# rgb-svid.net
KiCad netlist of a schematic drawn in EAGLE
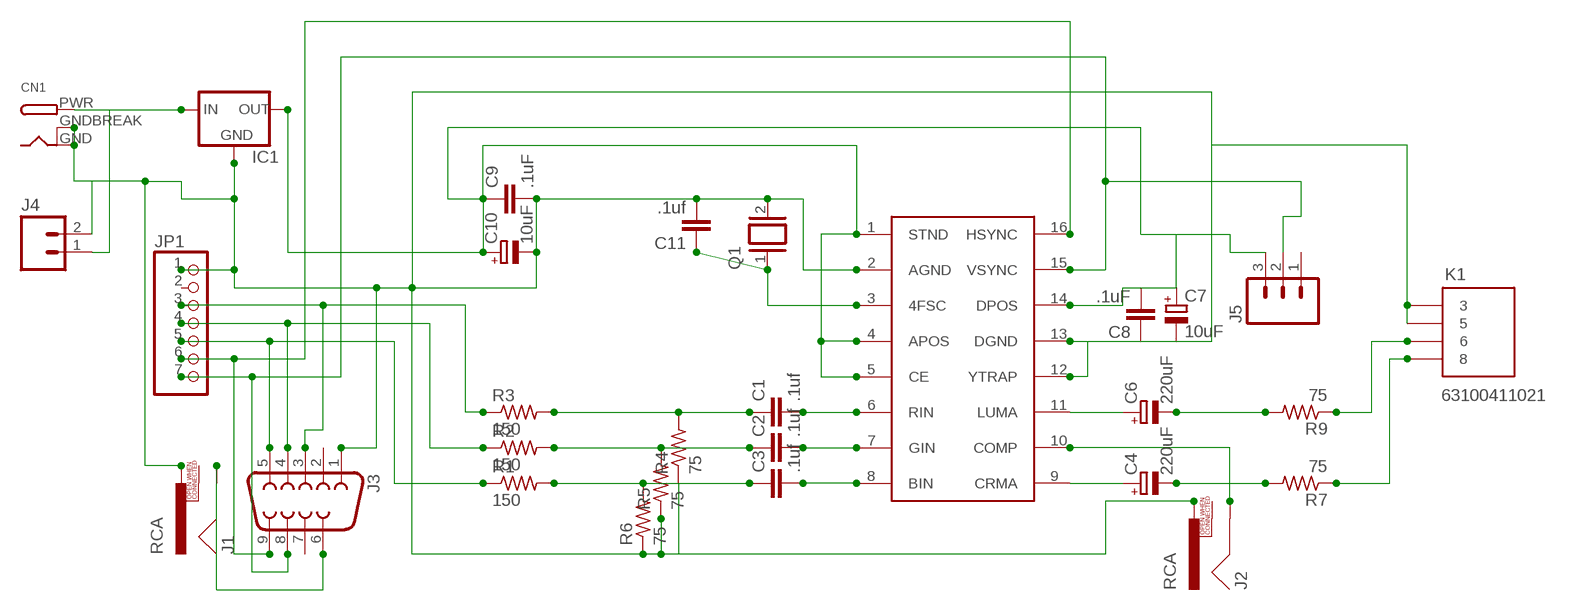
[diagram p0: schematic, sheet 1]

(export (version "E")
  (design (tool "Eeschema 10.0.6"))
  (components
    (comp (ref "C1")
      (value ".1uf")
      (footprint "eagle-import:C2.5-2")
      (libsource (lib "eagle-import") (part "C2.5/2"))
    )
    (comp (ref "C2")
      (value ".1uf")
      (footprint "eagle-import:C2.5-2")
      (libsource (lib "eagle-import") (part "C2.5/2"))
    )
    (comp (ref "C3")
      (value ".1uf")
      (footprint "eagle-import:C2.5-2")
      (libsource (lib "eagle-import") (part "C2.5/2"))
    )
    (comp (ref "C4")
      (value "220uF")
      (footprint "eagle-import:E2-5")
      (libsource (lib "eagle-import") (part "CPOL-EUE2-5"))
    )
    (comp (ref "C6")
      (value "220uF")
      (footprint "eagle-import:E2-5")
      (libsource (lib "eagle-import") (part "CPOL-EUE2-5"))
    )
    (comp (ref "C7")
      (value "10uF")
      (footprint "eagle-import:E2-5")
      (libsource (lib "eagle-import") (part "CPOL-EUE2-5"))
    )
    (comp (ref "C8")
      (value ".1uF")
      (footprint "eagle-import:C2.5-2")
      (libsource (lib "eagle-import") (part "C2.5/2"))
    )
    (comp (ref "C9")
      (value ".1uF")
      (footprint "eagle-import:C2.5-2")
      (libsource (lib "eagle-import") (part "C2.5/2"))
    )
    (comp (ref "C10")
      (value "10uF")
      (footprint "eagle-import:E2-5")
      (libsource (lib "eagle-import") (part "CPOL-EUE2-5"))
    )
    (comp (ref "C11")
      (value ".1uf")
      (footprint "eagle-import:C2.5-2")
      (libsource (lib "eagle-import") (part "C2.5/2"))
    )
    (comp (ref "CN1")
      (value "DCBARRELPTH")
      (footprint "eagle-import:DCJACK_2MM_PTH")
      (libsource (lib "eagle-import") (part "DCBARRELPTH"))
    )
    (comp (ref "IC1")
      (value "78XXL")
      (footprint "eagle-import:78XXL")
      (libsource (lib "eagle-import") (part "78XXL"))
    )
    (comp (ref "J1")
      (value "RCA")
      (footprint "eagle-import:RCA")
      (libsource (lib "eagle-import") (part "RCA"))
    )
    (comp (ref "J2")
      (value "RCA")
      (footprint "eagle-import:RCA")
      (libsource (lib "eagle-import") (part "RCA"))
    )
    (comp (ref "J3")
      (value "DB9FEMALE")
      (footprint "eagle-import:DB9")
      (libsource (lib "eagle-import") (part "DB9FEMALE"))
    )
    (comp (ref "J4")
      (value "M02LOCK")
      (footprint "eagle-import:1X02_LOCK")
      (libsource (lib "eagle-import") (part "M02LOCK"))
    )
    (comp (ref "J5")
      (value "M03PTH")
      (footprint "eagle-import:1X03")
      (libsource (lib "eagle-import") (part "M03PTH"))
    )
    (comp (ref "JP1")
      (value "PINHD-1X7")
      (footprint "eagle-import:1X07")
      (libsource (lib "eagle-import") (part "PINHD-1X7"))
    )
    (comp (ref "K1")
      (value "63100411021")
      (footprint "eagle-import:63100411021")
      (libsource (lib "eagle-import") (part "63100411021"))
    )
    (comp (ref "Q1")
      (value "XTAL/S")
      (footprint "eagle-import:QS")
      (libsource (lib "eagle-import") (part "XTAL/S"))
    )
    (comp (ref "R1")
      (value "150")
      (footprint "eagle-import:0207_12")
      (libsource (lib "eagle-import") (part "R-US_0207/12"))
    )
    (comp (ref "R2")
      (value "150")
      (footprint "eagle-import:0207_12")
      (libsource (lib "eagle-import") (part "R-US_0207/12"))
    )
    (comp (ref "R3")
      (value "150")
      (footprint "eagle-import:0207_12")
      (libsource (lib "eagle-import") (part "R-US_0207/12"))
    )
    (comp (ref "R4")
      (value "75")
      (footprint "eagle-import:0207_12")
      (libsource (lib "eagle-import") (part "R-US_0207/12"))
    )
    (comp (ref "R5")
      (value "75")
      (footprint "eagle-import:0207_12")
      (libsource (lib "eagle-import") (part "R-US_0207/12"))
    )
    (comp (ref "R6")
      (value "75")
      (footprint "eagle-import:0207_12")
      (libsource (lib "eagle-import") (part "R-US_0207/12"))
    )
    (comp (ref "R7")
      (value "75")
      (footprint "eagle-import:0207_12")
      (libsource (lib "eagle-import") (part "R-US_0207/12"))
    )
    (comp (ref "R9")
      (value "75")
      (footprint "eagle-import:0207_12")
      (libsource (lib "eagle-import") (part "R-US_0207/12"))
    )
    (comp (ref "U$1")
      (value "AD725")
      (footprint "eagle-import:SO16W")
      (libsource (lib "eagle-import") (part "AD725"))
    )
  )
  (nets
    (net (code "1") (name "Net-(C1-Pad1)") (class "Default")
      (node (ref "C1") (pin "1") (pinfunction "1_1") (pintype "passive"))
      (node (ref "R3") (pin "2") (pinfunction "2_2") (pintype "passive"))
      (node (ref "R4") (pin "2") (pinfunction "2_2") (pintype "passive"))
    )
    (net (code "2") (name "Net-(C2-Pad1)") (class "Default")
      (node (ref "C2") (pin "1") (pinfunction "1_1") (pintype "passive"))
      (node (ref "R2") (pin "2") (pinfunction "2_2") (pintype "passive"))
      (node (ref "R5") (pin "2") (pinfunction "2_2") (pintype "passive"))
    )
    (net (code "3") (name "Net-(C3-Pad1)") (class "Default")
      (node (ref "C3") (pin "1") (pinfunction "1_1") (pintype "passive"))
      (node (ref "R1") (pin "2") (pinfunction "2_2") (pintype "passive"))
      (node (ref "R6") (pin "2") (pinfunction "2_2") (pintype "passive"))
    )
    (net (code "4") (name "Net-(C4-Pad-)") (class "Default")
      (node (ref "C4") (pin "-") (pinfunction "-_-") (pintype "passive"))
      (node (ref "R7") (pin "2") (pinfunction "2_2") (pintype "passive"))
    )
    (net (code "5") (name "Net-(C6-Pad-)") (class "Default")
      (node (ref "C6") (pin "-") (pinfunction "-_-") (pintype "passive"))
      (node (ref "R9") (pin "2") (pinfunction "2_2") (pintype "passive"))
    )
    (net (code "6") (name "Net-(CN1-PadPWR)") (class "Default")
      (node (ref "CN1") (pin "PWR") (pinfunction "PWR_PWR") (pintype "power_in"))
      (node (ref "IC1") (pin "IN") (pinfunction "IN_IN") (pintype "input"))
      (node (ref "J4") (pin "1") (pinfunction "1_1") (pintype "passive"))
    )
    (net (code "7") (name "Net-(J1-PadSHELL)") (class "Default")
      (node (ref "J1") (pin "SHELL") (pinfunction "SHELL_SHELL") (pintype "bidirectional"))
      (node (ref "J3") (pin "6") (pinfunction "6_6") (pintype "passive"))
    )
    (net (code "8") (name "Net-(J3-Pad3)") (class "Default")
      (node (ref "J3") (pin "3") (pinfunction "3_3") (pintype "passive"))
      (node (ref "JP1") (pin "3") (pinfunction "3_3") (pintype "passive"))
      (node (ref "R3") (pin "1") (pinfunction "1_1") (pintype "passive"))
    )
    (net (code "9") (name "Net-(J3-Pad4)") (class "Default")
      (node (ref "J3") (pin "4") (pinfunction "4_4") (pintype "passive"))
      (node (ref "JP1") (pin "4") (pinfunction "4_4") (pintype "passive"))
      (node (ref "R2") (pin "1") (pinfunction "1_1") (pintype "passive"))
    )
    (net (code "10") (name "Net-(J3-Pad5)") (class "Default")
      (node (ref "J3") (pin "5") (pinfunction "5_5") (pintype "passive"))
      (node (ref "JP1") (pin "5") (pinfunction "5_5") (pintype "passive"))
      (node (ref "R1") (pin "1") (pinfunction "1_1") (pintype "passive"))
    )
    (net (code "11") (name "Net-(K1-Pad6)") (class "Default")
      (node (ref "K1") (pin "6") (pinfunction "6_6") (pintype "passive"))
      (node (ref "R9") (pin "1") (pinfunction "1_1") (pintype "passive"))
    )
    (net (code "12") (name "Net-(K1-Pad8)") (class "Default")
      (node (ref "K1") (pin "8") (pinfunction "8_8") (pintype "passive"))
      (node (ref "R7") (pin "1") (pinfunction "1_1") (pintype "passive"))
    )
    (net (code "13") (name "Net-(U$1-4FSC)") (class "Default")
      (node (ref "C11") (pin "1") (pinfunction "1_1") (pintype "passive"))
      (node (ref "Q1") (pin "1") (pinfunction "1_1") (pintype "passive"))
      (node (ref "U$1") (pin "3") (pinfunction "4FSC_3") (pintype "bidirectional"))
    )
    (net (code "14") (name "Net-(U$1-AGND)") (class "Default")
      (node (ref "C10") (pin "-") (pinfunction "-_-") (pintype "passive"))
      (node (ref "C11") (pin "2") (pinfunction "2_2") (pintype "passive"))
      (node (ref "C7") (pin "-") (pinfunction "-_-") (pintype "passive"))
      (node (ref "C8") (pin "1") (pinfunction "1_1") (pintype "passive"))
      (node (ref "C9") (pin "2") (pinfunction "2_2") (pintype "passive"))
      (node (ref "CN1") (pin "GND") (pinfunction "GND_GND") (pintype "power_in"))
      (node (ref "CN1") (pin "GNDBREAK") (pinfunction "GNDBREAK_GNDBREAK") (pintype "power_in"))
      (node (ref "IC1") (pin "GND") (pinfunction "GND_GND") (pintype "input"))
      (node (ref "J1") (pin "PIN") (pinfunction "PIN_PIN") (pintype "bidirectional"))
      (node (ref "J2") (pin "PIN") (pinfunction "PIN_PIN") (pintype "bidirectional"))
      (node (ref "J3") (pin "1") (pinfunction "1_1") (pintype "passive"))
      (node (ref "J4") (pin "2") (pinfunction "2_2") (pintype "passive"))
      (node (ref "JP1") (pin "1") (pinfunction "1_1") (pintype "passive"))
      (node (ref "K1") (pin "3") (pinfunction "3_3") (pintype "passive"))
      (node (ref "K1") (pin "5") (pinfunction "5_5") (pintype "passive"))
      (node (ref "Q1") (pin "2") (pinfunction "2_2") (pintype "passive"))
      (node (ref "R4") (pin "1") (pinfunction "1_1") (pintype "passive"))
      (node (ref "R5") (pin "1") (pinfunction "1_1") (pintype "passive"))
      (node (ref "R6") (pin "1") (pinfunction "1_1") (pintype "passive"))
      (node (ref "U$1") (pin "12") (pinfunction "YTRAP_12") (pintype "bidirectional"))
      (node (ref "U$1") (pin "13") (pinfunction "DGND_13") (pintype "bidirectional"))
      (node (ref "U$1") (pin "2") (pinfunction "AGND_2") (pintype "bidirectional"))
    )
    (net (code "15") (name "Net-(U$1-APOS)") (class "Default")
      (node (ref "C10") (pin "+") (pinfunction "+_+") (pintype "passive"))
      (node (ref "C7") (pin "+") (pinfunction "+_+") (pintype "passive"))
      (node (ref "C8") (pin "2") (pinfunction "2_2") (pintype "passive"))
      (node (ref "C9") (pin "1") (pinfunction "1_1") (pintype "passive"))
      (node (ref "IC1") (pin "OUT") (pinfunction "OUT_OUT") (pintype "passive"))
      (node (ref "J5") (pin "3") (pinfunction "3_3") (pintype "passive"))
      (node (ref "U$1") (pin "1") (pinfunction "STND_1") (pintype "bidirectional"))
      (node (ref "U$1") (pin "14") (pinfunction "DPOS_14") (pintype "bidirectional"))
      (node (ref "U$1") (pin "4") (pinfunction "APOS_4") (pintype "bidirectional"))
      (node (ref "U$1") (pin "5") (pinfunction "CE_5") (pintype "bidirectional"))
    )
    (net (code "16") (name "Net-(U$1-BIN)") (class "Default")
      (node (ref "C3") (pin "2") (pinfunction "2_2") (pintype "passive"))
      (node (ref "U$1") (pin "8") (pinfunction "BIN_8") (pintype "bidirectional"))
    )
    (net (code "17") (name "Net-(U$1-COMP)") (class "Default")
      (node (ref "J2") (pin "SHELL") (pinfunction "SHELL_SHELL") (pintype "bidirectional"))
      (node (ref "U$1") (pin "10") (pinfunction "COMP_10") (pintype "bidirectional"))
    )
    (net (code "18") (name "Net-(U$1-CRMA)") (class "Default")
      (node (ref "C4") (pin "+") (pinfunction "+_+") (pintype "passive"))
      (node (ref "U$1") (pin "9") (pinfunction "CRMA_9") (pintype "bidirectional"))
    )
    (net (code "19") (name "Net-(U$1-GIN)") (class "Default")
      (node (ref "C2") (pin "2") (pinfunction "2_2") (pintype "passive"))
      (node (ref "U$1") (pin "7") (pinfunction "GIN_7") (pintype "bidirectional"))
    )
    (net (code "20") (name "Net-(U$1-HSYNC)") (class "Default")
      (node (ref "J3") (pin "9") (pinfunction "9_9") (pintype "passive"))
      (node (ref "JP1") (pin "6") (pinfunction "6_6") (pintype "passive"))
      (node (ref "U$1") (pin "16") (pinfunction "HSYNC_16") (pintype "bidirectional"))
    )
    (net (code "21") (name "Net-(U$1-LUMA)") (class "Default")
      (node (ref "C6") (pin "+") (pinfunction "+_+") (pintype "passive"))
      (node (ref "U$1") (pin "11") (pinfunction "LUMA_11") (pintype "bidirectional"))
    )
    (net (code "22") (name "Net-(U$1-RIN)") (class "Default")
      (node (ref "C1") (pin "2") (pinfunction "2_2") (pintype "passive"))
      (node (ref "U$1") (pin "6") (pinfunction "RIN_6") (pintype "bidirectional"))
    )
    (net (code "23") (name "Net-(U$1-VSYNC)") (class "Default")
      (node (ref "J3") (pin "8") (pinfunction "8_8") (pintype "passive"))
      (node (ref "J5") (pin "2") (pinfunction "2_2") (pintype "passive"))
      (node (ref "JP1") (pin "7") (pinfunction "7_7") (pintype "passive"))
      (node (ref "U$1") (pin "15") (pinfunction "VSYNC_15") (pintype "bidirectional"))
    )
    (net (code "24") (name "unconnected-(J1-PadSWITCH)") (class "Default")
      (node (ref "J1") (pin "SWITCH") (pinfunction "SWITCH_SWITCH") (pintype "bidirectional"))
    )
    (net (code "25") (name "unconnected-(J2-PadSWITCH)") (class "Default")
      (node (ref "J2") (pin "SWITCH") (pinfunction "SWITCH_SWITCH") (pintype "bidirectional"))
    )
    (net (code "26") (name "unconnected-(J3-Pad2)") (class "Default")
      (node (ref "J3") (pin "2") (pinfunction "2_2") (pintype "passive"))
    )
    (net (code "27") (name "unconnected-(J3-Pad7)") (class "Default")
      (node (ref "J3") (pin "7") (pinfunction "7_7") (pintype "passive"))
    )
    (net (code "28") (name "unconnected-(J5-Pad1)") (class "Default")
      (node (ref "J5") (pin "1") (pinfunction "1_1") (pintype "passive"))
    )
    (net (code "29") (name "unconnected-(JP1-Pad2)") (class "Default")
      (node (ref "JP1") (pin "2") (pinfunction "2_2") (pintype "passive"))
    )
  )
)
